# Main.net
KiCad netlist of a schematic drawn in Altium Designer
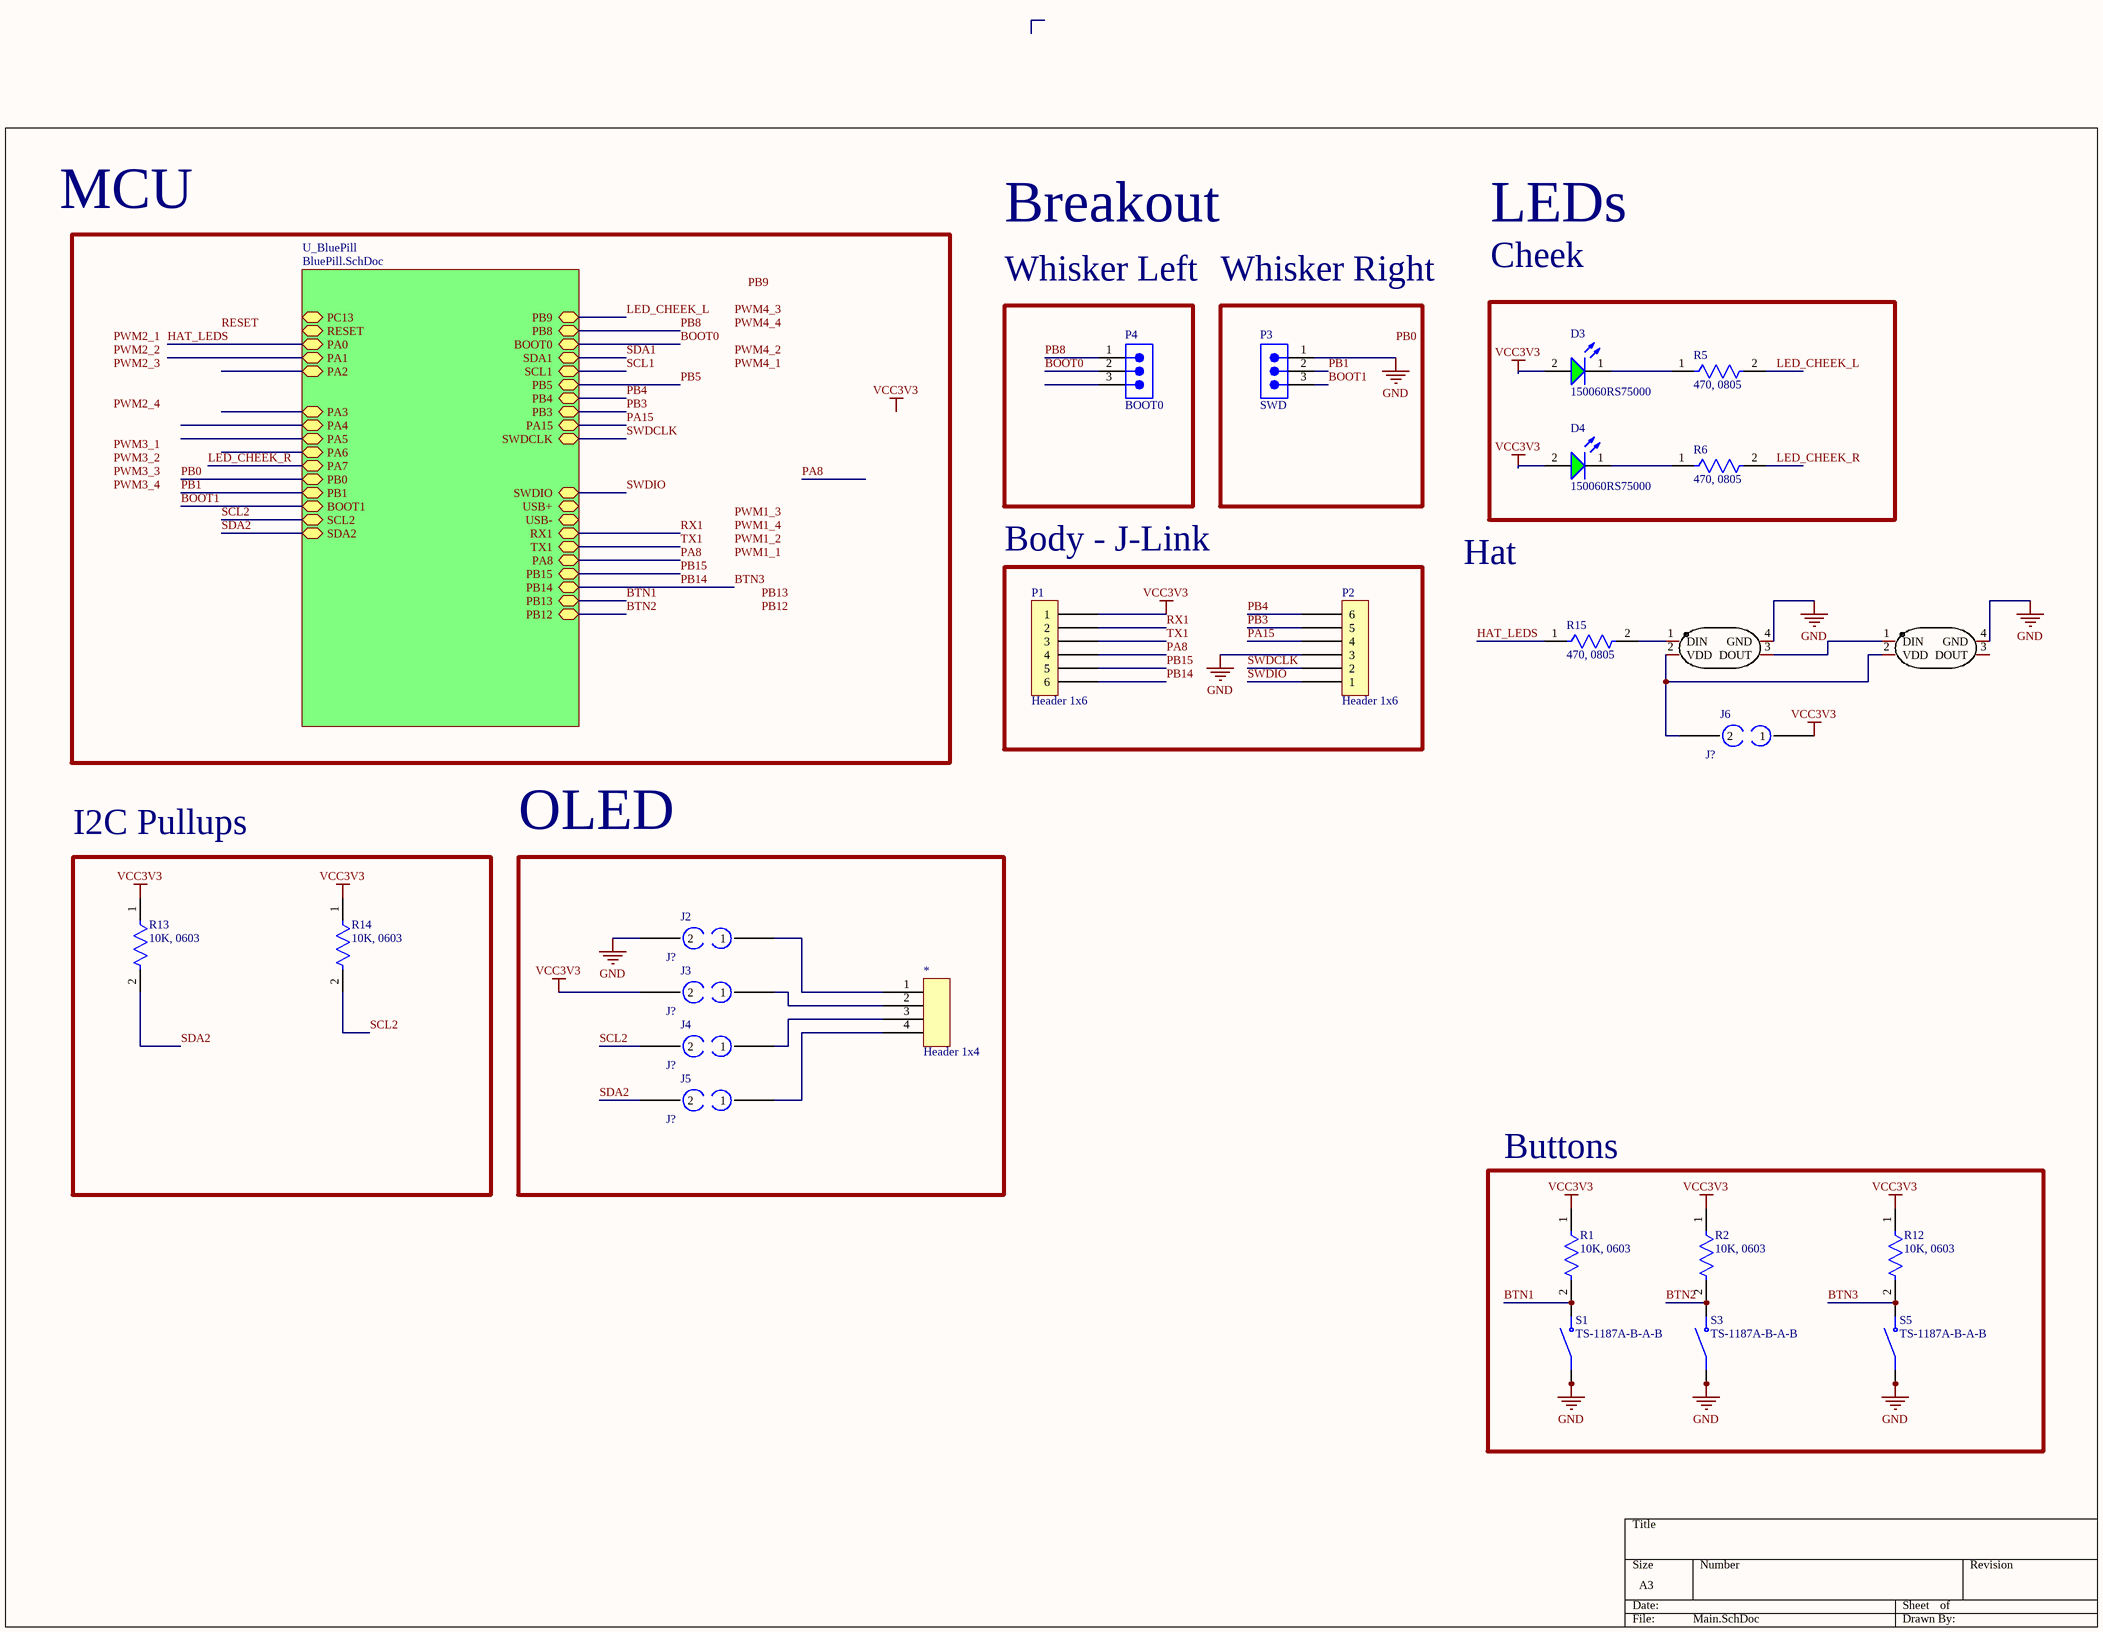
[diagram p0: Main.SchDoc]

(export (version "E")
  (design (tool "Eeschema 10.0.6"))
  (components
    (comp (ref "*")
      (value "Header 1x4")
      (footprint "Header 1x4")
      (libsource (lib "Headers") (part "Header 1x4"))
    )
    (comp (ref "D3")
      (value "150060RS75000")
      (footprint "WL-SMCW_0805_150080xx75000")
      (libsource (lib "Altium Content Vault") (part "LED_Green_2A-1K"))
    )
    (comp (ref "D4")
      (value "150060RS75000")
      (footprint "WL-SMCW_0805_150080xx75000")
      (libsource (lib "Altium Content Vault") (part "LED_Green_2A-1K"))
    )
    (comp (ref "J2")
      (value "J?")
      (footprint "SOLDER_BRIDGE_OPEN")
      (libsource (lib "GreyCat2K24 - 2") (part "Solder-Bridge-OPEN"))
    )
    (comp (ref "J3")
      (value "J?")
      (footprint "SOLDER_BRIDGE_OPEN")
      (libsource (lib "GreyCat2K24 - 2") (part "Solder-Bridge-OPEN"))
    )
    (comp (ref "J4")
      (value "J?")
      (footprint "SOLDER_BRIDGE_OPEN")
      (libsource (lib "GreyCat2K24 - 2") (part "Solder-Bridge-OPEN"))
    )
    (comp (ref "J5")
      (value "J?")
      (footprint "SOLDER_BRIDGE_OPEN")
      (libsource (lib "GreyCat2K24 - 2") (part "Solder-Bridge-OPEN"))
    )
    (comp (ref "J6")
      (value "J?")
      (footprint "SOLDER_BRIDGE_OPEN")
      (libsource (lib "GreyCat2K24 - 2") (part "Solder-Bridge-OPEN"))
    )
    (comp (ref "LED1")
      (value "SK6812SIDE-A-RVS")
      (footprint "LED-SMD_4P-L4.0-W1.6-L")
      (fields (field (name "MANUFACTURER") "欧思科光电"))
      (libsource (lib "altium-import") (part "root_0_SK6812SIDE-A-RVS_"))
    )
    (comp (ref "LED2")
      (value "SK6812SIDE-A-RVS")
      (footprint "LED-SMD_4P-L4.0-W1.6-L")
      (fields (field (name "MANUFACTURER") "欧思科光电"))
      (libsource (lib "altium-import") (part "root_0_SK6812SIDE-A-RVS_"))
    )
    (comp (ref "P1") (value "Header 1x6") (footprint "1x6_debug") (libsource (lib "*") (part "Header 1x6")))
    (comp (ref "P2") (value "Header 1x6") (footprint "1x6_debug") (libsource (lib "") (part "Header 1x6_1")))
    (comp (ref "P3")
      (value "SWD")
      (footprint "61300311121")
      (libsource (lib "Altium Content Vault") (part "Header_Male_1R_03P"))
    )
    (comp (ref "P4")
      (value "BOOT0")
      (footprint "61300311121")
      (libsource (lib "Altium Content Vault") (part "Header_Male_1R_03P"))
    )
    (comp (ref "R1")
      (value "10K, 0603")
      (footprint "FP-RC0603-0_55-IPC_C")
      (description "RES 10K OHM 1% 1/10W 0603")
      (fields (field (name "TOLERANCE") "1%"))
      (libsource (lib "Altium Content Vault") (part "1029c3af85768c4190bb7ad29bc67b5"))
    )
    (comp (ref "R2")
      (value "10K, 0603")
      (footprint "FP-RC0603-0_55-IPC_C")
      (description "RES 10K OHM 1% 1/10W 0603")
      (fields (field (name "TOLERANCE") "1%"))
      (libsource (lib "Altium Content Vault") (part "1029c3af85768c4190bb7ad29bc67b5"))
    )
    (comp (ref "R5")
      (value "470, 0805")
      (footprint "FP-RT0805-MFG")
      (description "RES SMD 470 OHM 1% 1/8W 0805")
      (fields
        (field (name "TOLERANCE") "0.0001")
        (field (name "MANUFACTURER PART NUMBER") "RT0805FRE07470RL")
      )
      (libsource (lib "Altium Content Vault") (part "1029c3af85768c4190bb7ad29bc67b5"))
    )
    (comp (ref "R6")
      (value "470, 0805")
      (footprint "FP-RT0805-MFG")
      (description "RES SMD 470 OHM 1% 1/8W 0805")
      (fields
        (field (name "TOLERANCE") "0.0001")
        (field (name "MANUFACTURER PART NUMBER") "RT0805FRE07470RL")
      )
      (libsource (lib "Altium Content Vault") (part "1029c3af85768c4190bb7ad29bc67b5"))
    )
    (comp (ref "R12")
      (value "10K, 0603")
      (footprint "FP-RC0603-0_55-IPC_C")
      (description "RES 10K OHM 1% 1/10W 0603")
      (fields (field (name "TOLERANCE") "1%"))
      (libsource (lib "Altium Content Vault") (part "1029c3af85768c4190bb7ad29bc67b5"))
    )
    (comp (ref "R13")
      (value "10K, 0603")
      (footprint "FP-RC0603-0_55-IPC_C")
      (description "RES 10K OHM 1% 1/10W 0603")
      (fields (field (name "TOLERANCE") "1%"))
      (libsource (lib "Altium Content Vault") (part "1029c3af85768c4190bb7ad29bc67b5"))
    )
    (comp (ref "R14")
      (value "10K, 0603")
      (footprint "FP-RC0603-0_55-IPC_C")
      (description "RES 10K OHM 1% 1/10W 0603")
      (fields (field (name "TOLERANCE") "1%"))
      (libsource (lib "Altium Content Vault") (part "1029c3af85768c4190bb7ad29bc67b5"))
    )
    (comp (ref "R15")
      (value "470, 0805")
      (footprint "FP-RT0805-MFG")
      (description "RES SMD 470 OHM 1% 1/8W 0805")
      (fields
        (field (name "TOLERANCE") "0.0001")
        (field (name "MANUFACTURER PART NUMBER") "RT0805FRE07470RL")
      )
      (libsource (lib "Altium Content Vault") (part "1029c3af85768c4190bb7ad29bc67b5"))
    )
    (comp (ref "S1")
      (value "TS-1187A-B-A-B")
      (footprint "SW_TS-1187A-B-A-B")
      (description "SPST 50mA @ 12VDC Top Actuated Round Button 160gf SMD Tactile Switches RoHS")
      (libsource (lib "Hornet 9 Altium") (part "TS-1187A-B-A-B"))
    )
    (comp (ref "S3")
      (value "TS-1187A-B-A-B")
      (footprint "SW_TS-1187A-B-A-B")
      (description "SPST 50mA @ 12VDC Top Actuated Round Button 160gf SMD Tactile Switches RoHS")
      (libsource (lib "Hornet 9 Altium") (part "TS-1187A-B-A-B"))
    )
    (comp (ref "S5")
      (value "TS-1187A-B-A-B")
      (footprint "SW_TS-1187A-B-A-B")
      (description "SPST 50mA @ 12VDC Top Actuated Round Button 160gf SMD Tactile Switches RoHS")
      (libsource (lib "Hornet 9 Altium") (part "TS-1187A-B-A-B"))
    )
  )
  (nets
    (net (code "1") (name "/BOOT0") (class "Default")
      (node (ref "P4") (pin "2") (pinfunction "2_2") (pintype "passive"))
    )
    (net (code "2") (name "/BOOT1") (class "Default")
      (node (ref "P3") (pin "3") (pinfunction "3_3") (pintype "passive"))
    )
    (net (code "3") (name "/BTN1") (class "Default")
      (node (ref "R1") (pin "2") (pinfunction "2_2") (pintype "passive"))
      (node (ref "S1") (pin "C") (pinfunction "NO_C") (pintype "passive"))
      (node (ref "S1") (pin "D") (pinfunction "NO_D") (pintype "passive"))
    )
    (net (code "4") (name "/BTN2") (class "Default")
      (node (ref "R2") (pin "2") (pinfunction "2_2") (pintype "passive"))
      (node (ref "S3") (pin "C") (pinfunction "NO_C") (pintype "passive"))
      (node (ref "S3") (pin "D") (pinfunction "NO_D") (pintype "passive"))
    )
    (net (code "5") (name "/BTN3") (class "Default")
      (node (ref "P1") (pin "6") (pinfunction "6_6") (pintype "passive"))
      (node (ref "R12") (pin "2") (pinfunction "2_2") (pintype "passive"))
      (node (ref "S5") (pin "C") (pinfunction "NO_C") (pintype "passive"))
      (node (ref "S5") (pin "D") (pinfunction "NO_D") (pintype "passive"))
    )
    (net (code "6") (name "/HAT_LEDS") (class "Default")
      (node (ref "R15") (pin "1") (pinfunction "1_1") (pintype "passive"))
    )
    (net (code "7") (name "/LED_CHEEK_L") (class "Default")
      (node (ref "R5") (pin "2") (pinfunction "2_2") (pintype "passive"))
    )
    (net (code "8") (name "/LED_CHEEK_R") (class "Default")
      (node (ref "R6") (pin "2") (pinfunction "2_2") (pintype "passive"))
    )
    (net (code "15") (name "/PA8") (class "Default")
      (node (ref "P1") (pin "4") (pinfunction "4_4") (pintype "passive"))
    )
    (net (code "16") (name "/PA15") (class "Default")
      (node (ref "P2") (pin "4") (pinfunction "4_4") (pintype "passive"))
    )
    (net (code "18") (name "/PB1") (class "Default")
      (node (ref "P3") (pin "2") (pinfunction "2_2") (pintype "passive"))
    )
    (net (code "19") (name "/PB3") (class "Default")
      (node (ref "P2") (pin "5") (pinfunction "5_5") (pintype "passive"))
    )
    (net (code "20") (name "/PB4") (class "Default")
      (node (ref "P2") (pin "6") (pinfunction "6_6") (pintype "passive"))
    )
    (net (code "22") (name "/PB8") (class "Default")
      (node (ref "P4") (pin "1") (pinfunction "1_1") (pintype "passive"))
    )
    (net (code "26") (name "/PB15") (class "Default")
      (node (ref "P1") (pin "5") (pinfunction "5_5") (pintype "passive"))
    )
    (net (code "46") (name "/RX1") (class "Default")
      (node (ref "P1") (pin "2") (pinfunction "2_2") (pintype "passive"))
    )
    (net (code "48") (name "/SCL2") (class "Default")
      (node (ref "J4") (pin "2") (pinfunction "2_2") (pintype "passive"))
      (node (ref "R14") (pin "2") (pinfunction "2_2") (pintype "passive"))
    )
    (net (code "50") (name "/SDA2") (class "Default")
      (node (ref "J5") (pin "2") (pinfunction "2_2") (pintype "passive"))
      (node (ref "R13") (pin "2") (pinfunction "2_2") (pintype "passive"))
    )
    (net (code "51") (name "/SWDCLK") (class "Default")
      (node (ref "P2") (pin "2") (pinfunction "2_2") (pintype "passive"))
    )
    (net (code "52") (name "/SWDIO") (class "Default")
      (node (ref "P2") (pin "1") (pinfunction "1_1") (pintype "passive"))
    )
    (net (code "53") (name "/TX1") (class "Default")
      (node (ref "P1") (pin "3") (pinfunction "3_3") (pintype "passive"))
    )
    (net (code "56") (name "GND") (class "Default")
      (node (ref "J2") (pin "2") (pinfunction "2_2") (pintype "passive"))
      (node (ref "LED1") (pin "4") (pinfunction "GND_4") (pintype "passive"))
      (node (ref "LED2") (pin "4") (pinfunction "GND_4") (pintype "passive"))
      (node (ref "P2") (pin "3") (pinfunction "3_3") (pintype "passive"))
      (node (ref "P3") (pin "1") (pinfunction "1_1") (pintype "passive"))
      (node (ref "S1") (pin "A") (pinfunction "COM_A") (pintype "passive"))
      (node (ref "S1") (pin "B") (pinfunction "COM_B") (pintype "passive"))
      (node (ref "S3") (pin "A") (pinfunction "COM_A") (pintype "passive"))
      (node (ref "S3") (pin "B") (pinfunction "COM_B") (pintype "passive"))
      (node (ref "S5") (pin "A") (pinfunction "COM_A") (pintype "passive"))
      (node (ref "S5") (pin "B") (pinfunction "COM_B") (pintype "passive"))
    )
    (net (code "57") (name "Net-(*-Pad1)") (class "Default")
      (node (ref "*") (pin "1") (pinfunction "1_1") (pintype "passive"))
      (node (ref "J2") (pin "1") (pinfunction "1_1") (pintype "passive"))
    )
    (net (code "58") (name "Net-(*-Pad2)") (class "Default")
      (node (ref "*") (pin "2") (pinfunction "2_2") (pintype "passive"))
      (node (ref "J3") (pin "1") (pinfunction "1_1") (pintype "passive"))
    )
    (net (code "59") (name "Net-(*-Pad3)") (class "Default")
      (node (ref "*") (pin "3") (pinfunction "3_3") (pintype "passive"))
      (node (ref "J4") (pin "1") (pinfunction "1_1") (pintype "passive"))
    )
    (net (code "60") (name "Net-(*-Pad4)") (class "Default")
      (node (ref "*") (pin "4") (pinfunction "4_4") (pintype "passive"))
      (node (ref "J5") (pin "1") (pinfunction "1_1") (pintype "passive"))
    )
    (net (code "61") (name "Net-(D3-K)") (class "Default")
      (node (ref "D3") (pin "1") (pinfunction "K_1") (pintype "passive"))
      (node (ref "R5") (pin "1") (pinfunction "1_1") (pintype "passive"))
    )
    (net (code "62") (name "Net-(D4-K)") (class "Default")
      (node (ref "D4") (pin "1") (pinfunction "K_1") (pintype "passive"))
      (node (ref "R6") (pin "1") (pinfunction "1_1") (pintype "passive"))
    )
    (net (code "63") (name "Net-(LED1-DIN)") (class "Default")
      (node (ref "LED1") (pin "1") (pinfunction "DIN_1") (pintype "passive"))
      (node (ref "R15") (pin "2") (pinfunction "2_2") (pintype "passive"))
    )
    (net (code "64") (name "Net-(LED1-DOUT)") (class "Default")
      (node (ref "LED1") (pin "3") (pinfunction "DOUT_3") (pintype "passive"))
      (node (ref "LED2") (pin "1") (pinfunction "DIN_1") (pintype "passive"))
    )
    (net (code "65") (name "Net-(LED1-VDD)") (class "Default")
      (node (ref "J6") (pin "2") (pinfunction "2_2") (pintype "passive"))
      (node (ref "LED1") (pin "2") (pinfunction "VDD_2") (pintype "passive"))
      (node (ref "LED2") (pin "2") (pinfunction "VDD_2") (pintype "passive"))
    )
    (net (code "66") (name "VCC3V3") (class "Default")
      (node (ref "D3") (pin "2") (pinfunction "A_2") (pintype "passive"))
      (node (ref "D4") (pin "2") (pinfunction "A_2") (pintype "passive"))
      (node (ref "J3") (pin "2") (pinfunction "2_2") (pintype "passive"))
      (node (ref "J6") (pin "1") (pinfunction "1_1") (pintype "passive"))
      (node (ref "P1") (pin "1") (pinfunction "1_1") (pintype "passive"))
      (node (ref "R1") (pin "1") (pinfunction "1_1") (pintype "passive"))
      (node (ref "R12") (pin "1") (pinfunction "1_1") (pintype "passive"))
      (node (ref "R13") (pin "1") (pinfunction "1_1") (pintype "passive"))
      (node (ref "R14") (pin "1") (pinfunction "1_1") (pintype "passive"))
      (node (ref "R2") (pin "1") (pinfunction "1_1") (pintype "passive"))
    )
    (net (code "67") (name "unconnected-(LED2-DOUT-Pad3)") (class "Default")
      (node (ref "LED2") (pin "3") (pinfunction "DOUT_3") (pintype "passive"))
    )
    (net (code "68") (name "unconnected-(P4-Pad3)") (class "Default")
      (node (ref "P4") (pin "3") (pinfunction "3_3") (pintype "passive"))
    )
  )
)
